# 1sqInchLogicAnalyzer.net
KiCad netlist of a schematic drawn in EAGLE
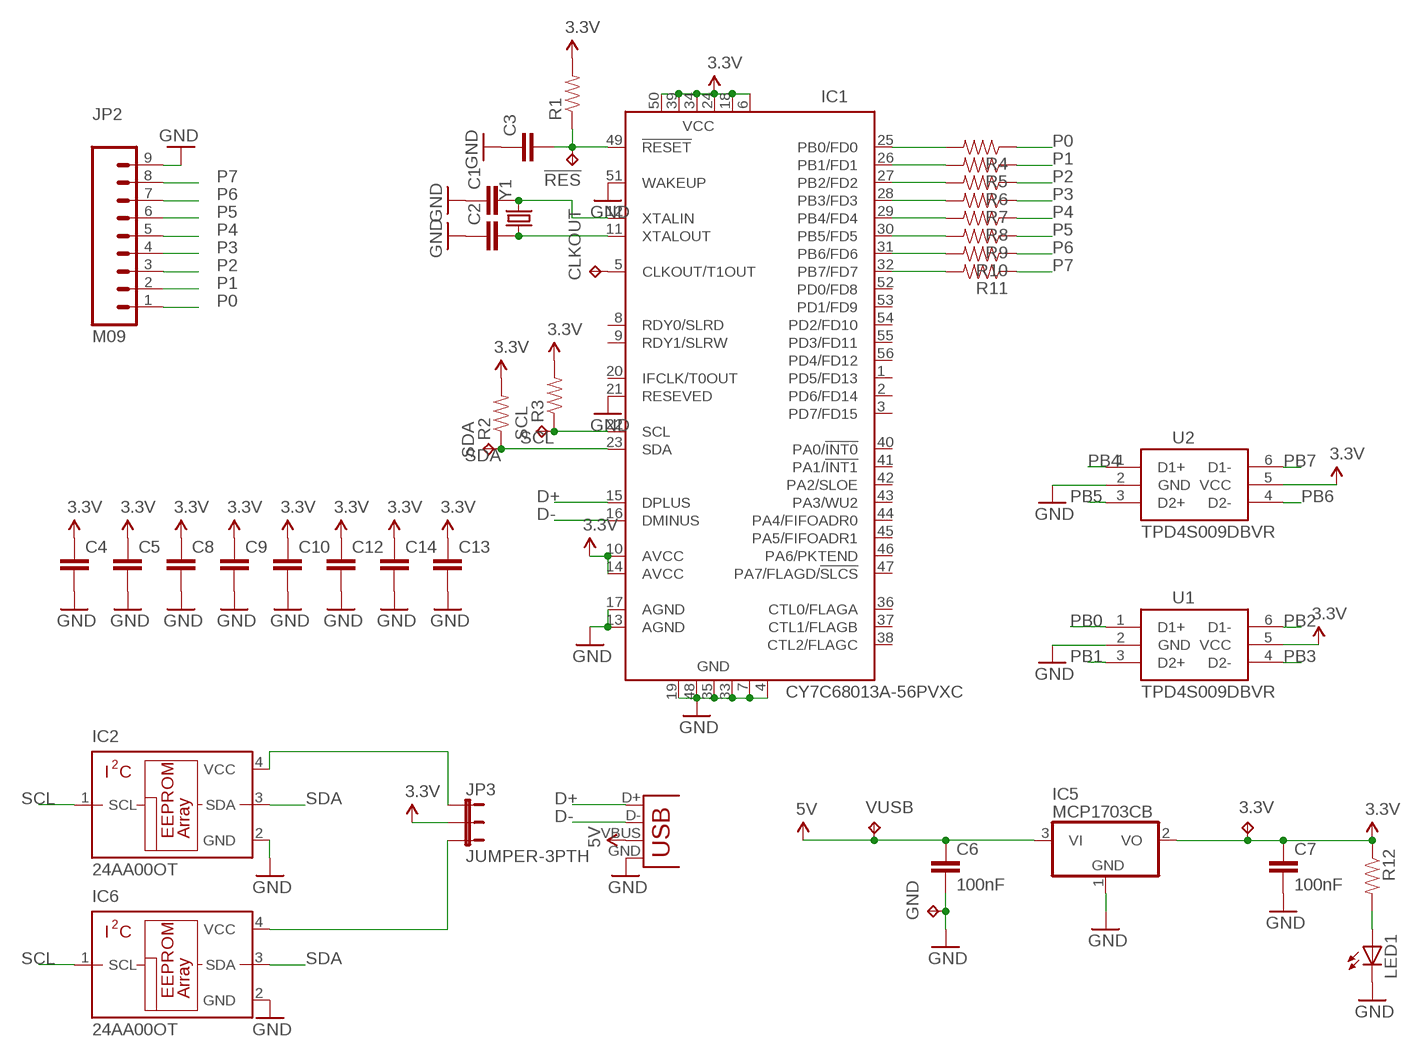
[diagram p0: schematic, sheet 1]

(export (version "E")
  (design (tool "Eeschema 10.0.6"))
  (components
    (comp (ref "!RES")
      (value "TPTP07R")
      (footprint "eagle-import:TP07R")
      (libsource (lib "eagle-import") (part "TPTP07R"))
    )
    (comp (ref "3.3V")
      (value "TPTP07R")
      (footprint "eagle-import:TP07R")
      (libsource (lib "eagle-import") (part "TPTP07R"))
    )
    (comp (ref "C1")
      (value "CAP0402-CAP")
      (footprint "eagle-import:0402-CAP")
      (libsource (lib "eagle-import") (part "CAP0402-CAP"))
    )
    (comp (ref "C2")
      (value "CAP0402-CAP")
      (footprint "eagle-import:0402-CAP")
      (libsource (lib "eagle-import") (part "CAP0402-CAP"))
    )
    (comp (ref "C3")
      (value "CAP0402-CAP")
      (footprint "eagle-import:0402-CAP")
      (libsource (lib "eagle-import") (part "CAP0402-CAP"))
    )
    (comp (ref "C4")
      (value "CAP0402-CAP")
      (footprint "eagle-import:0402-CAP")
      (libsource (lib "eagle-import") (part "CAP0402-CAP"))
    )
    (comp (ref "C5")
      (value "CAP0402-CAP")
      (footprint "eagle-import:0402-CAP")
      (libsource (lib "eagle-import") (part "CAP0402-CAP"))
    )
    (comp (ref "C6")
      (value "100nF")
      (footprint "eagle-import:0603-CAP")
      (libsource (lib "eagle-import") (part "CAP0603-CAP"))
    )
    (comp (ref "C7")
      (value "100nF")
      (footprint "eagle-import:0603-CAP")
      (libsource (lib "eagle-import") (part "CAP0603-CAP"))
    )
    (comp (ref "C8")
      (value "CAP0402-CAP")
      (footprint "eagle-import:0402-CAP")
      (libsource (lib "eagle-import") (part "CAP0402-CAP"))
    )
    (comp (ref "C9")
      (value "CAP0402-CAP")
      (footprint "eagle-import:0402-CAP")
      (libsource (lib "eagle-import") (part "CAP0402-CAP"))
    )
    (comp (ref "C10")
      (value "CAP0402-CAP")
      (footprint "eagle-import:0402-CAP")
      (libsource (lib "eagle-import") (part "CAP0402-CAP"))
    )
    (comp (ref "C12")
      (value "CAP0402-CAP")
      (footprint "eagle-import:0402-CAP")
      (libsource (lib "eagle-import") (part "CAP0402-CAP"))
    )
    (comp (ref "C13")
      (value "CAP0402-CAP")
      (footprint "eagle-import:0402-CAP")
      (libsource (lib "eagle-import") (part "CAP0402-CAP"))
    )
    (comp (ref "C14")
      (value "CAP0402-CAP")
      (footprint "eagle-import:0402-CAP")
      (libsource (lib "eagle-import") (part "CAP0402-CAP"))
    )
    (comp (ref "CLKOUT")
      (value "TPTP07R")
      (footprint "eagle-import:TP07R")
      (libsource (lib "eagle-import") (part "TPTP07R"))
    )
    (comp (ref "GND")
      (value "TPTP07R")
      (footprint "eagle-import:TP07R")
      (libsource (lib "eagle-import") (part "TPTP07R"))
    )
    (comp (ref "IC1")
      (value "CY7C68013A-56PVXC")
      (footprint "eagle-import:SSOP56")
      (fields (field (name "MF") "CYPRESS SEMICONDUCTOR CORPORAT"))
      (libsource (lib "eagle-import") (part "CY7C6801A-56PVXC3"))
    )
    (comp (ref "IC2")
      (value "24AA00OT")
      (footprint "eagle-import:SOT23-5L")
      (fields (field (name "MF") "MICROCHIP") (field (name "MPN") "24AA00T-I/OTG"))
      (libsource (lib "eagle-import") (part "2400OTAA"))
    )
    (comp (ref "IC5")
      (value "MCP1703CB")
      (footprint "eagle-import:SOT23")
      (libsource (lib "eagle-import") (part "MCP1703CB"))
    )
    (comp (ref "IC6")
      (value "24AA00OT")
      (footprint "eagle-import:SOT23-5L")
      (fields (field (name "MF") "MICROCHIP") (field (name "MPN") "24AA00T-I/OTG"))
      (libsource (lib "eagle-import") (part "2400OTAA"))
    )
    (comp (ref "JP2")
      (value "M09")
      (footprint "eagle-import:1X09")
      (libsource (lib "eagle-import") (part "M09"))
    )
    (comp (ref "JP3")
      (value "JUMPER-3PTH")
      (footprint "eagle-import:1X03")
      (libsource (lib "eagle-import") (part "JUMPER-3PTH"))
    )
    (comp (ref "LED1")
      (value "LED0603")
      (footprint "eagle-import:LED-0603")
      (libsource (lib "eagle-import") (part "LED0603"))
    )
    (comp (ref "R1")
      (value "RESISTOR0402-RES")
      (footprint "eagle-import:0402-RES")
      (libsource (lib "eagle-import") (part "RESISTOR0402-RES"))
    )
    (comp (ref "R2")
      (value "RESISTOR0402-RES")
      (footprint "eagle-import:0402-RES")
      (libsource (lib "eagle-import") (part "RESISTOR0402-RES"))
    )
    (comp (ref "R3")
      (value "RESISTOR0402-RES")
      (footprint "eagle-import:0402-RES")
      (libsource (lib "eagle-import") (part "RESISTOR0402-RES"))
    )
    (comp (ref "R4")
      (value "RESISTOR0402-RES")
      (footprint "eagle-import:0402-RES")
      (libsource (lib "eagle-import") (part "RESISTOR0402-RES"))
    )
    (comp (ref "R5")
      (value "RESISTOR0402-RES")
      (footprint "eagle-import:0402-RES")
      (libsource (lib "eagle-import") (part "RESISTOR0402-RES"))
    )
    (comp (ref "R6")
      (value "RESISTOR0402-RES")
      (footprint "eagle-import:0402-RES")
      (libsource (lib "eagle-import") (part "RESISTOR0402-RES"))
    )
    (comp (ref "R7")
      (value "RESISTOR0402-RES")
      (footprint "eagle-import:0402-RES")
      (libsource (lib "eagle-import") (part "RESISTOR0402-RES"))
    )
    (comp (ref "R8")
      (value "RESISTOR0402-RES")
      (footprint "eagle-import:0402-RES")
      (libsource (lib "eagle-import") (part "RESISTOR0402-RES"))
    )
    (comp (ref "R9")
      (value "RESISTOR0402-RES")
      (footprint "eagle-import:0402-RES")
      (libsource (lib "eagle-import") (part "RESISTOR0402-RES"))
    )
    (comp (ref "R10")
      (value "RESISTOR0402-RES")
      (footprint "eagle-import:0402-RES")
      (libsource (lib "eagle-import") (part "RESISTOR0402-RES"))
    )
    (comp (ref "R11")
      (value "RESISTOR0402-RES")
      (footprint "eagle-import:0402-RES")
      (libsource (lib "eagle-import") (part "RESISTOR0402-RES"))
    )
    (comp (ref "R12")
      (value "RESISTOR0402-RES")
      (footprint "eagle-import:0402-RES")
      (libsource (lib "eagle-import") (part "RESISTOR0402-RES"))
    )
    (comp (ref "SCL")
      (value "TPTP07R")
      (footprint "eagle-import:TP07R")
      (libsource (lib "eagle-import") (part "TPTP07R"))
    )
    (comp (ref "SDA")
      (value "TPTP07R")
      (footprint "eagle-import:TP07R")
      (libsource (lib "eagle-import") (part "TPTP07R"))
    )
    (comp (ref "U1")
      (value "TPD4S009DBVR")
      (footprint "eagle-import:TPD4S009DBVR")
      (libsource (lib "eagle-import") (part "TPD4S009DBVR"))
    )
    (comp (ref "U2")
      (value "TPD4S009DBVR")
      (footprint "eagle-import:TPD4S009DBVR")
      (libsource (lib "eagle-import") (part "TPD4S009DBVR"))
    )
    (comp (ref "VUSB")
      (value "TPTP07R")
      (footprint "eagle-import:TP07R")
      (libsource (lib "eagle-import") (part "TPTP07R"))
    )
    (comp (ref "X2")
      (value "USB-MICROB")
      (footprint "eagle-import:USB-MICROB")
      (libsource (lib "eagle-import") (part "USB-MICROB"))
    )
    (comp (ref "Y1")
      (value "CRYSTAL5X3")
      (footprint "eagle-import:CRYSTAL-SMD-5X3")
      (libsource (lib "eagle-import") (part "CRYSTAL5X3"))
    )
  )
  (nets
    (net (code "1") (name "/D+") (class "Default")
      (node (ref "IC1") (pin "15") (pinfunction "DPLUS_15") (pintype "bidirectional"))
      (node (ref "X2") (pin "D+") (pinfunction "D+_D+") (pintype "bidirectional"))
    )
    (net (code "2") (name "/D-") (class "Default")
      (node (ref "IC1") (pin "16") (pinfunction "DMINUS_16") (pintype "bidirectional"))
      (node (ref "X2") (pin "D-") (pinfunction "D-_D-") (pintype "bidirectional"))
    )
    (net (code "3") (name "/P0") (class "Default")
      (node (ref "JP2") (pin "1") (pinfunction "1_1") (pintype "passive"))
      (node (ref "R4") (pin "1") (pinfunction "1_1") (pintype "passive"))
    )
    (net (code "4") (name "/P1") (class "Default")
      (node (ref "JP2") (pin "2") (pinfunction "2_2") (pintype "passive"))
      (node (ref "R5") (pin "1") (pinfunction "1_1") (pintype "passive"))
    )
    (net (code "5") (name "/P2") (class "Default")
      (node (ref "JP2") (pin "3") (pinfunction "3_3") (pintype "passive"))
      (node (ref "R6") (pin "1") (pinfunction "1_1") (pintype "passive"))
    )
    (net (code "6") (name "/P3") (class "Default")
      (node (ref "JP2") (pin "4") (pinfunction "4_4") (pintype "passive"))
      (node (ref "R7") (pin "1") (pinfunction "1_1") (pintype "passive"))
    )
    (net (code "7") (name "/P4") (class "Default")
      (node (ref "JP2") (pin "5") (pinfunction "5_5") (pintype "passive"))
      (node (ref "R8") (pin "1") (pinfunction "1_1") (pintype "passive"))
    )
    (net (code "8") (name "/P5") (class "Default")
      (node (ref "JP2") (pin "6") (pinfunction "6_6") (pintype "passive"))
      (node (ref "R9") (pin "1") (pinfunction "1_1") (pintype "passive"))
    )
    (net (code "9") (name "/P6") (class "Default")
      (node (ref "JP2") (pin "7") (pinfunction "7_7") (pintype "passive"))
      (node (ref "R10") (pin "1") (pinfunction "1_1") (pintype "passive"))
    )
    (net (code "10") (name "/P7") (class "Default")
      (node (ref "JP2") (pin "8") (pinfunction "8_8") (pintype "passive"))
      (node (ref "R11") (pin "1") (pinfunction "1_1") (pintype "passive"))
    )
    (net (code "11") (name "/PB0") (class "Default")
      (node (ref "IC1") (pin "25") (pinfunction "PB0/FD0_25") (pintype "bidirectional"))
      (node (ref "R4") (pin "2") (pinfunction "2_2") (pintype "passive"))
      (node (ref "U1") (pin "1") (pinfunction "D1+_1") (pintype "bidirectional"))
    )
    (net (code "12") (name "/PB1") (class "Default")
      (node (ref "IC1") (pin "26") (pinfunction "PB1/FD1_26") (pintype "bidirectional"))
      (node (ref "R5") (pin "2") (pinfunction "2_2") (pintype "passive"))
      (node (ref "U1") (pin "3") (pinfunction "D2+_3") (pintype "bidirectional"))
    )
    (net (code "13") (name "/PB2") (class "Default")
      (node (ref "IC1") (pin "27") (pinfunction "PB2/FD2_27") (pintype "bidirectional"))
      (node (ref "R6") (pin "2") (pinfunction "2_2") (pintype "passive"))
      (node (ref "U1") (pin "6") (pinfunction "D1-_6") (pintype "bidirectional"))
    )
    (net (code "14") (name "/PB3") (class "Default")
      (node (ref "IC1") (pin "28") (pinfunction "PB3/FD3_28") (pintype "bidirectional"))
      (node (ref "R7") (pin "2") (pinfunction "2_2") (pintype "passive"))
      (node (ref "U1") (pin "4") (pinfunction "D2-_4") (pintype "bidirectional"))
    )
    (net (code "15") (name "/PB4") (class "Default")
      (node (ref "IC1") (pin "29") (pinfunction "PB4/FD4_29") (pintype "bidirectional"))
      (node (ref "R8") (pin "2") (pinfunction "2_2") (pintype "passive"))
      (node (ref "U2") (pin "1") (pinfunction "D1+_1") (pintype "bidirectional"))
    )
    (net (code "16") (name "/PB5") (class "Default")
      (node (ref "IC1") (pin "30") (pinfunction "PB5/FD5_30") (pintype "bidirectional"))
      (node (ref "R9") (pin "2") (pinfunction "2_2") (pintype "passive"))
      (node (ref "U2") (pin "3") (pinfunction "D2+_3") (pintype "bidirectional"))
    )
    (net (code "17") (name "/PB6") (class "Default")
      (node (ref "IC1") (pin "31") (pinfunction "PB6/FD6_31") (pintype "bidirectional"))
      (node (ref "R10") (pin "2") (pinfunction "2_2") (pintype "passive"))
      (node (ref "U2") (pin "4") (pinfunction "D2-_4") (pintype "bidirectional"))
    )
    (net (code "18") (name "/PB7") (class "Default")
      (node (ref "IC1") (pin "32") (pinfunction "PB7/FD7_32") (pintype "bidirectional"))
      (node (ref "R11") (pin "2") (pinfunction "2_2") (pintype "passive"))
      (node (ref "U2") (pin "6") (pinfunction "D1-_6") (pintype "bidirectional"))
    )
    (net (code "19") (name "/SCL") (class "Default")
      (node (ref "IC1") (pin "22") (pinfunction "SCL_22") (pintype "output"))
      (node (ref "IC2") (pin "1") (pinfunction "SCL_1") (pintype "input"))
      (node (ref "IC6") (pin "1") (pinfunction "SCL_1") (pintype "input"))
      (node (ref "R3") (pin "1") (pinfunction "1_1") (pintype "passive"))
      (node (ref "SCL") (pin "TP") (pinfunction "TP_TP") (pintype "input"))
    )
    (net (code "20") (name "/SDA") (class "Default")
      (node (ref "IC1") (pin "23") (pinfunction "SDA_23") (pintype "bidirectional"))
      (node (ref "IC2") (pin "3") (pinfunction "SDA_3") (pintype "bidirectional"))
      (node (ref "IC6") (pin "3") (pinfunction "SDA_3") (pintype "bidirectional"))
      (node (ref "R2") (pin "1") (pinfunction "1_1") (pintype "passive"))
      (node (ref "SDA") (pin "TP") (pinfunction "TP_TP") (pintype "input"))
    )
    (net (code "21") (name "3.3V") (class "Default")
      (node (ref "3.3V") (pin "TP") (pinfunction "TP_TP") (pintype "input"))
      (node (ref "C10") (pin "1") (pinfunction "1_1") (pintype "passive"))
      (node (ref "C12") (pin "1") (pinfunction "1_1") (pintype "passive"))
      (node (ref "C13") (pin "1") (pinfunction "1_1") (pintype "passive"))
      (node (ref "C14") (pin "1") (pinfunction "1_1") (pintype "passive"))
      (node (ref "C4") (pin "1") (pinfunction "1_1") (pintype "passive"))
      (node (ref "C5") (pin "1") (pinfunction "1_1") (pintype "passive"))
      (node (ref "C7") (pin "1") (pinfunction "1_1") (pintype "passive"))
      (node (ref "C8") (pin "1") (pinfunction "1_1") (pintype "passive"))
      (node (ref "C9") (pin "1") (pinfunction "1_1") (pintype "passive"))
      (node (ref "IC1") (pin "10") (pinfunction "AVCC_10") (pintype "input"))
      (node (ref "IC1") (pin "14") (pinfunction "AVCC_14") (pintype "input"))
      (node (ref "IC1") (pin "18") (pinfunction "VCC_18") (pintype "input"))
      (node (ref "IC1") (pin "24") (pinfunction "VCC_24") (pintype "input"))
      (node (ref "IC1") (pin "34") (pinfunction "VCC_34") (pintype "input"))
      (node (ref "IC1") (pin "39") (pinfunction "VCC_39") (pintype "input"))
      (node (ref "IC1") (pin "50") (pinfunction "VCC_50") (pintype "input"))
      (node (ref "IC1") (pin "6") (pinfunction "VCC_6") (pintype "input"))
      (node (ref "IC5") (pin "2") (pinfunction "VO_2") (pintype "passive"))
      (node (ref "JP3") (pin "2") (pinfunction "2_2") (pintype "passive"))
      (node (ref "R1") (pin "2") (pinfunction "2_2") (pintype "passive"))
      (node (ref "R12") (pin "1") (pinfunction "1_1") (pintype "passive"))
      (node (ref "R2") (pin "2") (pinfunction "2_2") (pintype "passive"))
      (node (ref "R3") (pin "2") (pinfunction "2_2") (pintype "passive"))
      (node (ref "U1") (pin "5") (pinfunction "VCC_5") (pintype "bidirectional"))
      (node (ref "U2") (pin "5") (pinfunction "VCC_5") (pintype "bidirectional"))
    )
    (net (code "22") (name "5V") (class "Default")
      (node (ref "C6") (pin "1") (pinfunction "1_1") (pintype "passive"))
      (node (ref "IC5") (pin "3") (pinfunction "VI_3") (pintype "input"))
      (node (ref "VUSB") (pin "TP") (pinfunction "TP_TP") (pintype "input"))
      (node (ref "X2") (pin "VBUS") (pinfunction "VBUS_VBUS") (pintype "bidirectional"))
    )
    (net (code "23") (name "GND") (class "Default")
      (node (ref "C1") (pin "1") (pinfunction "1_1") (pintype "passive"))
      (node (ref "C10") (pin "2") (pinfunction "2_2") (pintype "passive"))
      (node (ref "C12") (pin "2") (pinfunction "2_2") (pintype "passive"))
      (node (ref "C13") (pin "2") (pinfunction "2_2") (pintype "passive"))
      (node (ref "C14") (pin "2") (pinfunction "2_2") (pintype "passive"))
      (node (ref "C2") (pin "1") (pinfunction "1_1") (pintype "passive"))
      (node (ref "C3") (pin "1") (pinfunction "1_1") (pintype "passive"))
      (node (ref "C4") (pin "2") (pinfunction "2_2") (pintype "passive"))
      (node (ref "C5") (pin "2") (pinfunction "2_2") (pintype "passive"))
      (node (ref "C6") (pin "2") (pinfunction "2_2") (pintype "passive"))
      (node (ref "C7") (pin "2") (pinfunction "2_2") (pintype "passive"))
      (node (ref "C8") (pin "2") (pinfunction "2_2") (pintype "passive"))
      (node (ref "C9") (pin "2") (pinfunction "2_2") (pintype "passive"))
      (node (ref "GND") (pin "TP") (pinfunction "TP_TP") (pintype "input"))
      (node (ref "IC1") (pin "13") (pinfunction "AGND_13") (pintype "input"))
      (node (ref "IC1") (pin "17") (pinfunction "AGND_17") (pintype "input"))
      (node (ref "IC1") (pin "19") (pinfunction "GND_19") (pintype "input"))
      (node (ref "IC1") (pin "21") (pinfunction "RESEVED_21") (pintype "input"))
      (node (ref "IC1") (pin "33") (pinfunction "GND_33") (pintype "input"))
      (node (ref "IC1") (pin "35") (pinfunction "GND_35") (pintype "input"))
      (node (ref "IC1") (pin "4") (pinfunction "GND_4") (pintype "input"))
      (node (ref "IC1") (pin "48") (pinfunction "GND_48") (pintype "input"))
      (node (ref "IC1") (pin "51") (pinfunction "WAKEUP_51") (pintype "input"))
      (node (ref "IC1") (pin "7") (pinfunction "GND_7") (pintype "input"))
      (node (ref "IC2") (pin "2") (pinfunction "GND_2") (pintype "power_in"))
      (node (ref "IC5") (pin "1") (pinfunction "GND_1") (pintype "passive"))
      (node (ref "IC6") (pin "2") (pinfunction "GND_2") (pintype "power_in"))
      (node (ref "JP2") (pin "9") (pinfunction "9_9") (pintype "passive"))
      (node (ref "LED1") (pin "C") (pinfunction "C_C") (pintype "passive"))
      (node (ref "U1") (pin "2") (pinfunction "GND_2") (pintype "bidirectional"))
      (node (ref "U2") (pin "2") (pinfunction "GND_2") (pintype "bidirectional"))
      (node (ref "X2") (pin "GND") (pinfunction "GND_GND") (pintype "bidirectional"))
    )
    (net (code "24") (name "Net-(IC1-CLKOUT{slash}T1OUT)") (class "Default")
      (node (ref "CLKOUT") (pin "TP") (pinfunction "TP_TP") (pintype "input"))
      (node (ref "IC1") (pin "5") (pinfunction "CLKOUT/T1OUT_5") (pintype "input"))
    )
    (net (code "25") (name "Net-(IC1-XTALIN)") (class "Default")
      (node (ref "C1") (pin "2") (pinfunction "2_2") (pintype "passive"))
      (node (ref "IC1") (pin "12") (pinfunction "XTALIN_12") (pintype "input"))
      (node (ref "Y1") (pin "3") (pinfunction "2_3") (pintype "passive"))
    )
    (net (code "26") (name "Net-(IC1-XTALOUT)") (class "Default")
      (node (ref "C2") (pin "2") (pinfunction "2_2") (pintype "passive"))
      (node (ref "IC1") (pin "11") (pinfunction "XTALOUT_11") (pintype "input"))
      (node (ref "Y1") (pin "1") (pinfunction "1_1") (pintype "passive"))
    )
    (net (code "27") (name "Net-(IC1-~{RESET})") (class "Default")
      (node (ref "!RES") (pin "TP") (pinfunction "TP_TP") (pintype "input"))
      (node (ref "C3") (pin "2") (pinfunction "2_2") (pintype "passive"))
      (node (ref "IC1") (pin "49") (pinfunction "~{RESET}_49") (pintype "input"))
      (node (ref "R1") (pin "1") (pinfunction "1_1") (pintype "passive"))
    )
    (net (code "28") (name "Net-(IC2-VCC)") (class "Default")
      (node (ref "IC2") (pin "4") (pinfunction "VCC_4") (pintype "power_in"))
      (node (ref "JP3") (pin "1") (pinfunction "1_1") (pintype "passive"))
    )
    (net (code "29") (name "Net-(IC6-VCC)") (class "Default")
      (node (ref "IC6") (pin "4") (pinfunction "VCC_4") (pintype "power_in"))
      (node (ref "JP3") (pin "3") (pinfunction "3_3") (pintype "passive"))
    )
    (net (code "30") (name "Net-(LED1-PadA)") (class "Default")
      (node (ref "LED1") (pin "A") (pinfunction "A_A") (pintype "passive"))
      (node (ref "R12") (pin "2") (pinfunction "2_2") (pintype "passive"))
    )
    (net (code "31") (name "unconnected-(IC1-CTL0{slash}FLAGA-Pad36)") (class "Default")
      (node (ref "IC1") (pin "36") (pinfunction "CTL0/FLAGA_36") (pintype "output"))
    )
    (net (code "32") (name "unconnected-(IC1-CTL1{slash}FLAGB-Pad37)") (class "Default")
      (node (ref "IC1") (pin "37") (pinfunction "CTL1/FLAGB_37") (pintype "output"))
    )
    (net (code "33") (name "unconnected-(IC1-CTL2{slash}FLAGC-Pad38)") (class "Default")
      (node (ref "IC1") (pin "38") (pinfunction "CTL2/FLAGC_38") (pintype "output"))
    )
    (net (code "34") (name "unconnected-(IC1-IFCLK{slash}T0OUT-Pad20)") (class "Default")
      (node (ref "IC1") (pin "20") (pinfunction "IFCLK/T0OUT_20") (pintype "bidirectional"))
    )
    (net (code "35") (name "unconnected-(IC1-PA0{slash}~{INT0}-Pad40)") (class "Default")
      (node (ref "IC1") (pin "40") (pinfunction "PA0/~{INT0}_40") (pintype "bidirectional"))
    )
    (net (code "36") (name "unconnected-(IC1-PA1{slash}~{INT1}-Pad41)") (class "Default")
      (node (ref "IC1") (pin "41") (pinfunction "PA1/~{INT1}_41") (pintype "bidirectional"))
    )
    (net (code "37") (name "unconnected-(IC1-PA2{slash}SLOE-Pad42)") (class "Default")
      (node (ref "IC1") (pin "42") (pinfunction "PA2/SLOE_42") (pintype "bidirectional"))
    )
    (net (code "38") (name "unconnected-(IC1-PA3{slash}WU2-Pad43)") (class "Default")
      (node (ref "IC1") (pin "43") (pinfunction "PA3/WU2_43") (pintype "bidirectional"))
    )
    (net (code "39") (name "unconnected-(IC1-PA4{slash}FIFOADR0-Pad44)") (class "Default")
      (node (ref "IC1") (pin "44") (pinfunction "PA4/FIFOADR0_44") (pintype "bidirectional"))
    )
    (net (code "40") (name "unconnected-(IC1-PA5{slash}FIFOADR1-Pad45)") (class "Default")
      (node (ref "IC1") (pin "45") (pinfunction "PA5/FIFOADR1_45") (pintype "bidirectional"))
    )
    (net (code "41") (name "unconnected-(IC1-PA6{slash}PKTEND-Pad46)") (class "Default")
      (node (ref "IC1") (pin "46") (pinfunction "PA6/PKTEND_46") (pintype "bidirectional"))
    )
    (net (code "42") (name "unconnected-(IC1-PA7{slash}FLAGD{slash}~{SLCS}-Pad47)") (class "Default")
      (node (ref "IC1") (pin "47") (pinfunction "PA7/FLAGD/~{SLCS}_47") (pintype "bidirectional"))
    )
    (net (code "43") (name "unconnected-(IC1-PD0{slash}FD8-Pad52)") (class "Default")
      (node (ref "IC1") (pin "52") (pinfunction "PD0/FD8_52") (pintype "bidirectional"))
    )
    (net (code "44") (name "unconnected-(IC1-PD1{slash}FD9-Pad53)") (class "Default")
      (node (ref "IC1") (pin "53") (pinfunction "PD1/FD9_53") (pintype "bidirectional"))
    )
    (net (code "45") (name "unconnected-(IC1-PD2{slash}FD10-Pad54)") (class "Default")
      (node (ref "IC1") (pin "54") (pinfunction "PD2/FD10_54") (pintype "bidirectional"))
    )
    (net (code "46") (name "unconnected-(IC1-PD3{slash}FD11-Pad55)") (class "Default")
      (node (ref "IC1") (pin "55") (pinfunction "PD3/FD11_55") (pintype "bidirectional"))
    )
    (net (code "47") (name "unconnected-(IC1-PD4{slash}FD12-Pad56)") (class "Default")
      (node (ref "IC1") (pin "56") (pinfunction "PD4/FD12_56") (pintype "bidirectional"))
    )
    (net (code "48") (name "unconnected-(IC1-PD5{slash}FD13-Pad1)") (class "Default")
      (node (ref "IC1") (pin "1") (pinfunction "PD5/FD13_1") (pintype "bidirectional"))
    )
    (net (code "49") (name "unconnected-(IC1-PD6{slash}FD14-Pad2)") (class "Default")
      (node (ref "IC1") (pin "2") (pinfunction "PD6/FD14_2") (pintype "bidirectional"))
    )
    (net (code "50") (name "unconnected-(IC1-PD7{slash}FD15-Pad3)") (class "Default")
      (node (ref "IC1") (pin "3") (pinfunction "PD7/FD15_3") (pintype "bidirectional"))
    )
    (net (code "51") (name "unconnected-(IC1-RDY0{slash}SLRD-Pad8)") (class "Default")
      (node (ref "IC1") (pin "8") (pinfunction "RDY0/SLRD_8") (pintype "input"))
    )
    (net (code "52") (name "unconnected-(IC1-RDY1{slash}SLRW-Pad9)") (class "Default")
      (node (ref "IC1") (pin "9") (pinfunction "RDY1/SLRW_9") (pintype "input"))
    )
  )
)
